# DS133-1_0-B.net
KiCad netlist of a schematic drawn in Altium Designer
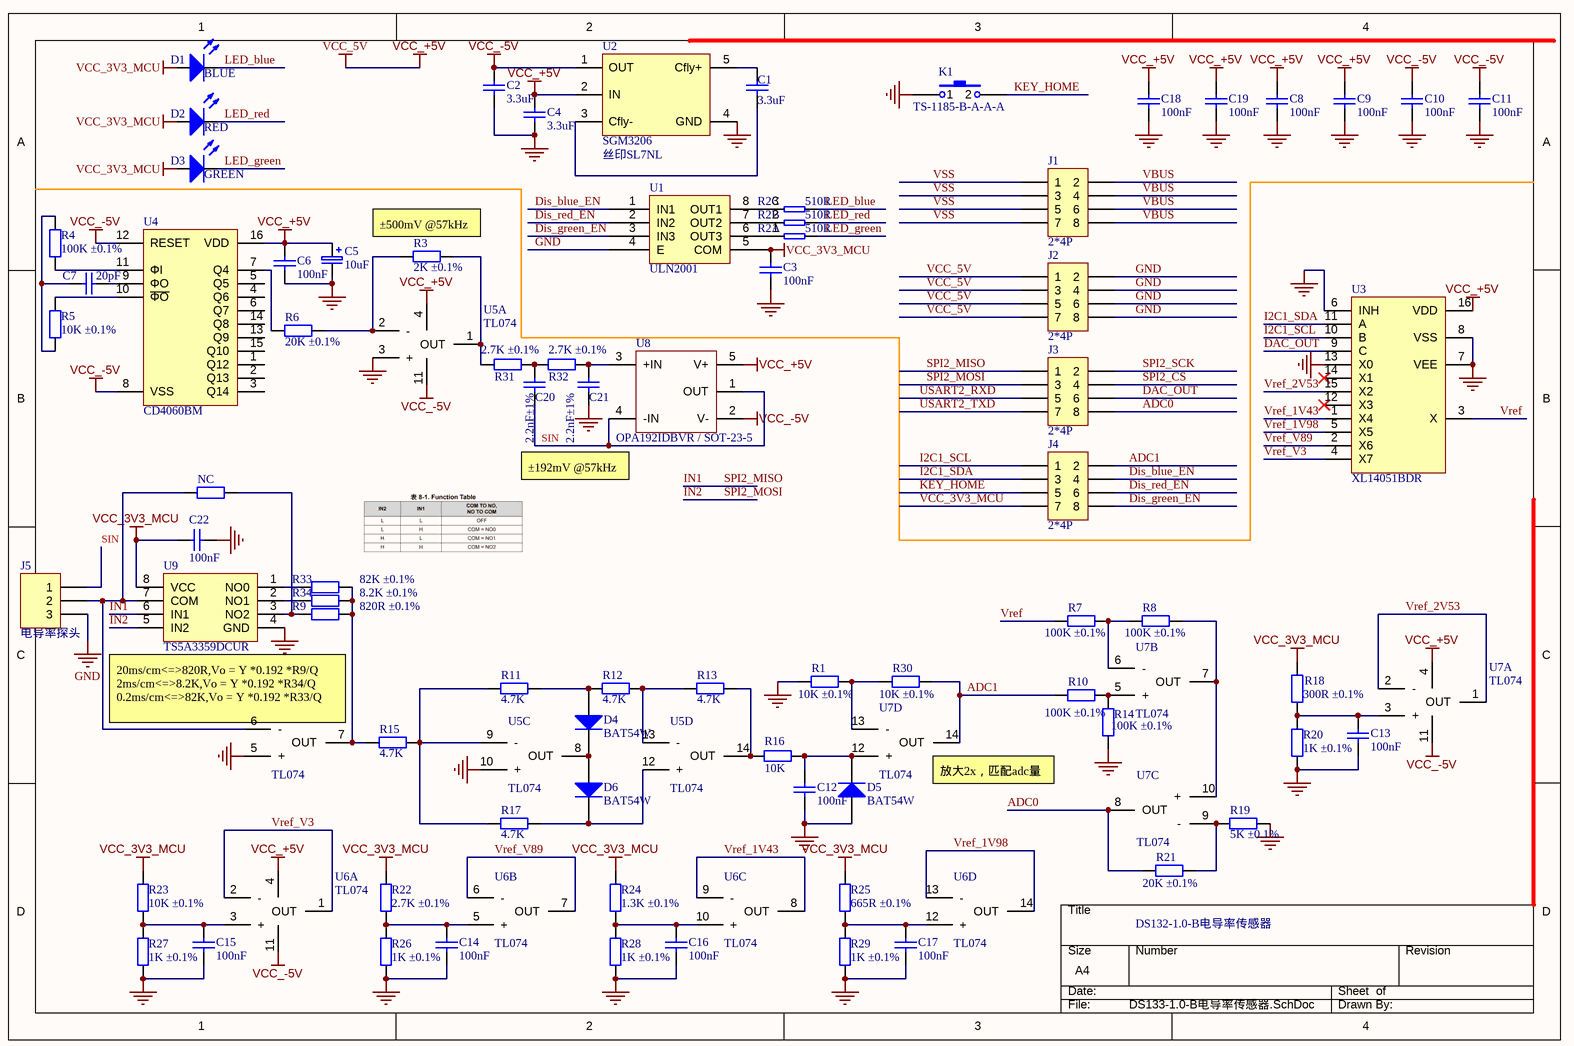
[diagram p0: DS133-1.0-B电导率传感器.SchDoc]

(export (version "E")
  (design (tool "Eeschema 10.0.6"))
  (components
    (comp (ref "C1")
      (value "3.3uF")
      (footprint "0603CAP")
      (description "贴片电容")
      (fields (field (name "Comment") "MLCC 3.3uF 50V ±10％ 0603"))
      (libsource (lib "AD_SCH") (part "MLCC 3.3uF 50V ±10％ 0603"))
    )
    (comp (ref "C2")
      (value "3.3uF")
      (footprint "0603CAP")
      (description "贴片电容")
      (libsource (lib "AD_SCH") (part "MLCC 3.3uF 50V ±10％ 0603"))
    )
    (comp (ref "C3")
      (value "100nF")
      (footprint "0603CAP")
      (description "贴片电容")
      (libsource (lib "AD_SCH") (part "MLCC 100nF 50V ±10％ 0603"))
    )
    (comp (ref "C4")
      (value "3.3uF")
      (footprint "0603CAP")
      (description "贴片电容")
      (fields (field (name "Comment") "MLCC 3.3uF 50V ±10％ 0603"))
      (libsource (lib "AD_SCH") (part "MLCC 3.3uF 50V ±10％ 0603"))
    )
    (comp (ref "C5")
      (value "10uF")
      (footprint "AVX_3216-18(1206)_SMD")
      (description "钽电容")
      (fields (field (name "Comment") "AVX_10uF/16V ±10％(C106)"))
      (libsource (lib "AD_SCH") (part "AVX_10uF/16V ±10％(C106)"))
    )
    (comp (ref "C6")
      (value "100nF")
      (footprint "0603CAP")
      (description "贴片电容")
      (fields (field (name "Comment") "SMDCAP00013"))
      (libsource (lib "AD_SCH") (part "MLCC 100nF 50V ±10％ 0603"))
    )
    (comp (ref "C7")
      (value "20pF")
      (footprint "0603CAP")
      (description "贴片电容")
      (fields (field (name "Comment") "SMDCAP00002"))
      (libsource (lib "AD_SCH") (part "MLCC 20pF 50V ±10％ 0603"))
    )
    (comp (ref "C8")
      (value "100nF")
      (footprint "0603CAP")
      (description "贴片电容")
      (libsource (lib "AD_SCH") (part "MLCC 100nF 50V ±10％ 0603"))
    )
    (comp (ref "C9")
      (value "100nF")
      (footprint "0603CAP")
      (description "贴片电容")
      (libsource (lib "AD_SCH") (part "MLCC 100nF 50V ±10％ 0603"))
    )
    (comp (ref "C10")
      (value "100nF")
      (footprint "0603CAP")
      (description "贴片电容")
      (libsource (lib "AD_SCH") (part "MLCC 100nF 50V ±10％ 0603"))
    )
    (comp (ref "C11")
      (value "100nF")
      (footprint "0603CAP")
      (description "贴片电容")
      (libsource (lib "AD_SCH") (part "MLCC 100nF 50V ±10％ 0603"))
    )
    (comp (ref "C12")
      (value "100nF")
      (footprint "0603CAP")
      (description "贴片电容")
      (libsource (lib "AD_SCH") (part "MLCC 100nF 50V ±10％ 0603"))
    )
    (comp (ref "C13")
      (value "100nF")
      (footprint "0603CAP")
      (description "贴片电容")
      (libsource (lib "AD_SCH") (part "MLCC 100nF 50V ±10％ 0603"))
    )
    (comp (ref "C14")
      (value "100nF")
      (footprint "0603CAP")
      (description "贴片电容")
      (libsource (lib "AD_SCH") (part "MLCC 100nF 50V ±10％ 0603"))
    )
    (comp (ref "C15")
      (value "100nF")
      (footprint "0603CAP")
      (description "贴片电容")
      (libsource (lib "AD_SCH") (part "MLCC 100nF 50V ±10％ 0603"))
    )
    (comp (ref "C16")
      (value "100nF")
      (footprint "0603CAP")
      (description "贴片电容")
      (libsource (lib "AD_SCH") (part "MLCC 100nF 50V ±10％ 0603"))
    )
    (comp (ref "C17")
      (value "100nF")
      (footprint "0603CAP")
      (description "贴片电容")
      (libsource (lib "AD_SCH") (part "MLCC 100nF 50V ±10％ 0603"))
    )
    (comp (ref "C18")
      (value "100nF")
      (footprint "0603CAP")
      (description "贴片电容")
      (libsource (lib "AD_SCH") (part "MLCC 100nF 50V ±10％ 0603"))
    )
    (comp (ref "C19")
      (value "100nF")
      (footprint "0603CAP")
      (description "贴片电容")
      (libsource (lib "AD_SCH") (part "MLCC 100nF 50V ±10％ 0603"))
    )
    (comp (ref "C20")
      (value "2.2nF±1%")
      (footprint "0603CAP")
      (description "贴片电容")
      (fields (field (name "Comment") "MLCC 2.2nF 50V ±1％ 0603"))
      (libsource (lib "AD_SCH") (part "MLCC 2.2nF 50V ±1％ 0603"))
    )
    (comp (ref "C21")
      (value "2.2nF±1%")
      (footprint "0603CAP")
      (description "贴片电容")
      (fields (field (name "Comment") "MLCC 2.2nF 50V ±1％ 0603"))
      (libsource (lib "AD_SCH") (part "MLCC 2.2nF 50V ±1％ 0603"))
    )
    (comp (ref "C22")
      (value "100nF")
      (footprint "0603CAP")
      (description "贴片电容")
      (libsource (lib "AD_SCH") (part "MLCC 100nF 50V ±10％ 0603"))
    )
    (comp (ref "D1")
      (value "BLUE")
      (footprint "LED_0805")
      (description "贴片LED")
      (fields (field (name "Comment") "SMDLED00010"))
      (libsource (lib "AD_SCH") (part "Chip 蓝色LED 0805"))
    )
    (comp (ref "D2")
      (value "RED")
      (footprint "LED_0805")
      (description "贴片LED")
      (fields (field (name "Comment") "SMDLED00003"))
      (libsource (lib "AD_SCH") (part "Chip 红色LED 0805"))
    )
    (comp (ref "D3")
      (value "GREEN")
      (footprint "LED_0805")
      (description "贴片LED")
      (fields (field (name "Comment") "Chip 翠绿LED 0805"))
      (libsource (lib "AD_SCH") (part "Chip 翠绿LED 0805"))
    )
    (comp (ref "D4") (value "BAT54W") (footprint "SOD-123") (libsource (lib "AD_SCH") (part "BAT54W")))
    (comp (ref "D5") (value "BAT54W") (footprint "SOD-123") (libsource (lib "AD_SCH") (part "BAT54W")))
    (comp (ref "D6") (value "BAT54W") (footprint "SOD-123") (libsource (lib "AD_SCH") (part "BAT54W")))
    (comp (ref "J1")
      (value "2*4P")
      (footprint "X1321WVS-2x04J-C40D53")
      (description "双排针2x4P 立贴 1.27mm")
      (fields (field (name "Comment") "X1321WVS-2x04J-C40D53"))
      (libsource (lib "AD_SCH") (part "X1321WVS-2x04J-C40D53"))
    )
    (comp (ref "J2")
      (value "2*4P")
      (footprint "X1321WVS-2x04J-C40D53")
      (description "双排针2x4P 立贴 1.27mm")
      (fields (field (name "Comment") "X1321WVS-2x04J-C40D53"))
      (libsource (lib "AD_SCH") (part "X1321WVS-2x04J-C40D53"))
    )
    (comp (ref "J3")
      (value "2*4P")
      (footprint "X1321WVS-2x04J-C40D53")
      (description "双排针2x4P 立贴 1.27mm")
      (fields (field (name "Comment") "X1321WVS-2x04J-C40D53"))
      (libsource (lib "AD_SCH") (part "X1321WVS-2x04J-C40D53"))
    )
    (comp (ref "J4")
      (value "2*4P")
      (footprint "X1321WVS-2x04J-C40D53")
      (description "双排针2x4P 立贴 1.27mm")
      (fields (field (name "Comment") "X1321WVS-2x04J-C40D53"))
      (libsource (lib "AD_SCH") (part "X1321WVS-2x04J-C40D53"))
    )
    (comp (ref "J5")
      (value "电导率探头")
      (footprint "SIP3")
      (description "单排直针")
      (fields (field (name "Comment") "SL000000042"))
      (libsource (lib "AD_SCH") (part "DIP3 单排直针 间距2.54mm 针长11mm 铜"))
    )
    (comp (ref "K1")
      (value "TS-1185-B-A-A-A")
      (footprint "KEY_TS-1185-x-A-A-A")
      (description "轻触开关")
      (libsource (lib "AD_SCH") (part "TS-1185-B-A-A-A"))
    )
    (comp (ref "NC")
      (value "Chip 0R 1/16W ±1％ 0603")
      (footprint "0603RES")
      (description "贴片电阻")
      (libsource (lib "AD_SCH") (part "Chip 0R 1/16W ±1％ 0603"))
    )
    (comp (ref "R1")
      (value "10K ±0.1%")
      (footprint "0603RES")
      (fields (field (name "Comment") "Chip 10K 1/10W ±0.1％ 0603"))
      (libsource (lib "AD_SCH") (part "Chip 10K 1/10W ±0.1％ 0603"))
    )
    (comp (ref "R2")
      (value "510R")
      (footprint "0603RES_Pack4")
      (description "贴片排阻")
      (fields (field (name "Comment") "SMDRES05003"))
      (libsource (lib "AD_SCH") (part "Chip R*4 510R 1/16W ±5％ 0603"))
    )
    (comp (ref "R3")
      (value "2K ±0.1%")
      (footprint "0603RES")
      (fields (field (name "Comment") "Chip 2K 1/10W ±0.1％ 0603"))
      (libsource (lib "AD_SCH") (part "Chip 2K 1/10W ±0.1％ 0603"))
    )
    (comp (ref "R4")
      (value "100K ±0.1%")
      (footprint "0603RES")
      (libsource (lib "AD_SCH") (part "Chip 100K 1/10W ±0.1％ 0603"))
    )
    (comp (ref "R5")
      (value "10K ±0.1%")
      (footprint "0603RES")
      (fields (field (name "Comment") "Chip 10K 1/10W ±0.1％ 0603"))
      (libsource (lib "") (part "Chip 10K 1/10W ±0.1％ 0603_1"))
    )
    (comp (ref "R6")
      (value "20K ±0.1%")
      (footprint "0603RES")
      (fields (field (name "Comment") "Chip 20K 1/10W ±0.1％ 0603"))
      (libsource (lib "AD_SCH") (part "Chip 20K 1/10W ±0.1％ 0603"))
    )
    (comp (ref "R7")
      (value "100K ±0.1%")
      (footprint "0603RES")
      (fields (field (name "Comment") "Chip 100K 1/10W ±0.1％ 0603"))
      (libsource (lib "") (part "Chip 100K 1/10W ±0.1％ 0603_1"))
    )
    (comp (ref "R8")
      (value "100K ±0.1%")
      (footprint "0603RES")
      (fields (field (name "Comment") "Chip 100K 1/10W ±0.1％ 0603"))
      (libsource (lib "") (part "Chip 100K 1/10W ±0.1％ 0603_2"))
    )
    (comp (ref "R9")
      (value "820R ±0.1%")
      (footprint "0603RES")
      (fields (field (name "Comment") "Chip 820R 1/10W ±0.1％ 0603"))
      (libsource (lib "AD_SCH") (part "Chip 820R 1/10W ±0.1％ 0603"))
    )
    (comp (ref "R10")
      (value "100K ±0.1%")
      (footprint "0603RES")
      (fields (field (name "Comment") "Chip 100K 1/10W ±0.1％ 0603"))
      (libsource (lib "") (part "Chip 100K 1/10W ±0.1％ 0603_1"))
    )
    (comp (ref "R11")
      (value "4.7K")
      (footprint "0603RES")
      (description "贴片电阻")
      (fields (field (name "Comment") "SMDRES00047"))
      (libsource (lib "AD_SCH") (part "Chip 4.7K 1/10W ±1％ 0603"))
    )
    (comp (ref "R12")
      (value "4.7K")
      (footprint "0603RES")
      (description "贴片电阻")
      (fields (field (name "Comment") "SMDRES00047"))
      (libsource (lib "AD_SCH") (part "Chip 4.7K 1/10W ±1％ 0603"))
    )
    (comp (ref "R13")
      (value "4.7K")
      (footprint "0603RES")
      (description "贴片电阻")
      (fields (field (name "Comment") "SMDRES00047"))
      (libsource (lib "AD_SCH") (part "Chip 4.7K 1/10W ±1％ 0603"))
    )
    (comp (ref "R14")
      (value "100K ±0.1%")
      (footprint "0603RES")
      (fields (field (name "Comment") "Chip 100K 1/10W ±0.1％ 0603"))
      (libsource (lib "AD_SCH") (part "Chip 100K 1/10W ±0.1％ 0603"))
    )
    (comp (ref "R15")
      (value "4.7K")
      (footprint "0603RES")
      (description "贴片电阻")
      (fields (field (name "Comment") "SMDRES00047"))
      (libsource (lib "AD_SCH") (part "Chip 4.7K 1/10W ±1％ 0603"))
    )
    (comp (ref "R16")
      (value "10K")
      (footprint "0603RES")
      (description "贴片电阻")
      (fields (field (name "Comment") "Chip 10K 1/16W ±1％ 0603"))
      (libsource (lib "AD_SCH") (part "Chip 10K 1/16W ±1％ 0603"))
    )
    (comp (ref "R17")
      (value "4.7K")
      (footprint "0603RES")
      (description "贴片电阻")
      (fields (field (name "Comment") "SMDRES00047"))
      (libsource (lib "AD_SCH") (part "Chip 4.7K 1/10W ±1％ 0603"))
    )
    (comp (ref "R18")
      (value "300R ±0.1%")
      (footprint "0603RES")
      (libsource (lib "AD_SCH") (part "Chip 300R 1/10W ±0.1％ 0603"))
    )
    (comp (ref "R19")
      (value "5K ±0.1%")
      (footprint "0603RES")
      (fields (field (name "Comment") "Chip 5K 1/10W ±0.1％ 0603"))
      (libsource (lib "AD_SCH") (part "Chip 5K 1/10W ±0.1％ 0603"))
    )
    (comp (ref "R20")
      (value "1K ±0.1%")
      (footprint "0603RES")
      (fields (field (name "Comment") "Chip 1K 1/10W ±0.1％ 0603"))
      (libsource (lib "AD_SCH") (part "Chip 1K 1/10W ±0.1％ 0603"))
    )
    (comp (ref "R21")
      (value "20K ±0.1%")
      (footprint "0603RES")
      (fields (field (name "Comment") "Chip 20K 1/10W ±0.1％ 0603"))
      (libsource (lib "AD_SCH") (part "Chip 20K 1/10W ±0.1％ 0603"))
    )
    (comp (ref "R22")
      (value "2.7K ±0.1%")
      (footprint "0603RES")
      (fields (field (name "Comment") "Chip 2.7K 1/10W ±0.1％ 0603"))
      (libsource (lib "") (part "Chip 2.7K 1/10W ±0.1％ 0603_1"))
    )
    (comp (ref "R23")
      (value "10K ±0.1%")
      (footprint "0603RES")
      (fields (field (name "Comment") "Chip 10K 1/10W ±0.1％ 0603"))
      (libsource (lib "") (part "Chip 10K 1/10W ±0.1％ 0603_1"))
    )
    (comp (ref "R24")
      (value "1.3K ±0.1%")
      (footprint "0603RES")
      (fields (field (name "Comment") "Chip 1.3K 1/10W ±0.1％ 0603"))
      (libsource (lib "AD_SCH") (part "Chip 1.3K 1/10W ±0.1％ 0603"))
    )
    (comp (ref "R25")
      (value "665R ±0.1%")
      (footprint "0603RES")
      (fields (field (name "Comment") "Chip 665R 1/10W ±0.1％ 0603"))
      (libsource (lib "AD_SCH") (part "Chip 665R 1/10W ±0.1％ 0603"))
    )
    (comp (ref "R26")
      (value "1K ±0.1%")
      (footprint "0603RES")
      (fields (field (name "Comment") "Chip 1K 1/10W ±0.1％ 0603"))
      (libsource (lib "AD_SCH") (part "Chip 1K 1/10W ±0.1％ 0603"))
    )
    (comp (ref "R27")
      (value "1K ±0.1%")
      (footprint "0603RES")
      (fields (field (name "Comment") "Chip 1K 1/10W ±0.1％ 0603"))
      (libsource (lib "AD_SCH") (part "Chip 1K 1/10W ±0.1％ 0603"))
    )
    (comp (ref "R28")
      (value "1K ±0.1%")
      (footprint "0603RES")
      (fields (field (name "Comment") "Chip 1K 1/10W ±0.1％ 0603"))
      (libsource (lib "AD_SCH") (part "Chip 1K 1/10W ±0.1％ 0603"))
    )
    (comp (ref "R29")
      (value "1K ±0.1%")
      (footprint "0603RES")
      (fields (field (name "Comment") "Chip 1K 1/10W ±0.1％ 0603"))
      (libsource (lib "AD_SCH") (part "Chip 1K 1/10W ±0.1％ 0603"))
    )
    (comp (ref "R30")
      (value "10K ±0.1%")
      (footprint "0603RES")
      (fields (field (name "Comment") "Chip 10K 1/10W ±0.1％ 0603"))
      (libsource (lib "AD_SCH") (part "Chip 10K 1/10W ±0.1％ 0603"))
    )
    (comp (ref "R31")
      (value "2.7K ±0.1%")
      (footprint "0603RES")
      (fields (field (name "Comment") "Chip 2.7K 1/10W ±0.1％ 0603"))
      (libsource (lib "AD_SCH") (part "Chip 2.7K 1/10W ±0.1％ 0603"))
    )
    (comp (ref "R32")
      (value "2.7K ±0.1%")
      (footprint "0603RES")
      (fields (field (name "Comment") "Chip 2.7K 1/10W ±0.1％ 0603"))
      (libsource (lib "AD_SCH") (part "Chip 2.7K 1/10W ±0.1％ 0603"))
    )
    (comp (ref "R33")
      (value "82K ±0.1%")
      (footprint "0603RES")
      (fields (field (name "Comment") "SMDRES00096"))
      (libsource (lib "AD_SCH") (part "Chip 82K 1/10W ±0.1％ 0603"))
    )
    (comp (ref "R34")
      (value "8.2K ±0.1%")
      (footprint "0603RES")
      (fields (field (name "Comment") "Chip 8.2k 1/10W ±0.1％ 0603"))
      (libsource (lib "AD_SCH") (part "Chip 8.2k 1/10W ±0.1％ 0603"))
    )
    (comp (ref "U1")
      (value "ULN2001")
      (footprint "SO-8")
      (description "电机驱动芯片")
      (fields (field (name "Comment") "SMDIC000018"))
      (libsource (lib "AD_SCH") (part "ULN2001 SOP-8"))
    )
    (comp (ref "U2")
      (value "SGM3206")
      (footprint "SOT23-5")
      (description "电荷泵芯片")
      (fields (field (name "ALTIUM_VALUE") "丝印SL7NL"))
      (libsource (lib "AD_SCH") (part "SGM3206"))
    )
    (comp (ref "U3")
      (value "XL14051BDR")
      (footprint "SO-16")
      (description "XINLUDA(信路达)\r\nXL14051BDR\r\nSOP-16​")
      (libsource (lib "AD_SCH") (part "XL14051BDR"))
    )
    (comp (ref "U4")
      (value "CD4060BM")
      (footprint "SO-16")
      (description "HGSEMI(华冠)\r\nCD4060BM/TR\r\nSOP-16")
      (libsource (lib "AD_SCH") (part "CD4060BM"))
    )
    (comp (ref "U5")
      (value "TL074")
      (footprint "SO-14")
      (description "TI\r\nTL074CDR\r\nSOIC-14")
      (libsource (lib "AD_SCH") (part "TL074"))
    )
    (comp (ref "U6")
      (value "TL074")
      (footprint "SO-14")
      (description "TI\r\nTL074CDR\r\nSOIC-14")
      (libsource (lib "AD_SCH") (part "TL074"))
    )
    (comp (ref "U7")
      (value "TL074")
      (footprint "SO-14")
      (description "TI\r\nTL074CDR\r\nSOIC-14")
      (libsource (lib "AD_SCH") (part "TL074"))
    )
    (comp (ref "U8")
      (value "OPA192IDBVR / SOT-23-5")
      (footprint "SOT23-5")
      (description "低失调电压: 65 µV（最大值）\r\n低输入偏置电流: 1 pA（最大值）\r\n单电源供电：2.7 V至5.5 V")
      (libsource (lib "AD_SCH") (part "AD8605"))
    )
    (comp (ref "U9")
      (value "TS5A3359DCUR")
      (footprint "VSSOP-8")
      (description "单刀三掷(SP3T)模拟开关")
      (libsource (lib "AD_SCH") (part "TS5A3359DCUR"))
    )
  )
  (nets
    (net (code "1") (name "/ADC0") (class "Default")
      (node (ref "J3") (pin "8") (pinfunction "8_8") (pintype "passive"))
      (node (ref "R21") (pin "1") (pinfunction "1_1") (pintype "passive"))
      (node (ref "U7") (pin "8") (pinfunction "OUT_8") (pintype "passive"))
    )
    (net (code "2") (name "/ADC1") (class "Default")
      (node (ref "J4") (pin "2") (pinfunction "2_2") (pintype "passive"))
      (node (ref "R10") (pin "1") (pinfunction "1_1") (pintype "passive"))
      (node (ref "R30") (pin "2") (pinfunction "2_2") (pintype "passive"))
      (node (ref "U7") (pin "14") (pinfunction "OUT_14") (pintype "passive"))
    )
    (net (code "3") (name "/DAC_OUT") (class "Default")
      (node (ref "J3") (pin "6") (pinfunction "6_6") (pintype "passive"))
      (node (ref "U3") (pin "9") (pinfunction "C_9") (pintype "passive"))
    )
    (net (code "4") (name "/Dis_blue_EN") (class "Default")
      (node (ref "J4") (pin "4") (pinfunction "4_4") (pintype "passive"))
      (node (ref "U1") (pin "1") (pinfunction "IN1_1") (pintype "passive"))
    )
    (net (code "5") (name "/Dis_green_EN") (class "Default")
      (node (ref "J4") (pin "8") (pinfunction "8_8") (pintype "passive"))
      (node (ref "U1") (pin "3") (pinfunction "IN3_3") (pintype "passive"))
    )
    (net (code "6") (name "/Dis_red_EN") (class "Default")
      (node (ref "J4") (pin "6") (pinfunction "6_6") (pintype "passive"))
      (node (ref "U1") (pin "2") (pinfunction "IN2_2") (pintype "passive"))
    )
    (net (code "7") (name "/I2C1_SCL") (class "Default")
      (node (ref "J4") (pin "1") (pinfunction "1_1") (pintype "passive"))
      (node (ref "U3") (pin "10") (pinfunction "B_10") (pintype "passive"))
    )
    (net (code "8") (name "/I2C1_SDA") (class "Default")
      (node (ref "J4") (pin "3") (pinfunction "3_3") (pintype "passive"))
      (node (ref "U3") (pin "11") (pinfunction "A_11") (pintype "passive"))
    )
    (net (code "9") (name "/IN1") (class "Default")
      (node (ref "J3") (pin "1") (pinfunction "1_1") (pintype "passive"))
      (node (ref "U9") (pin "6") (pinfunction "IN1_6") (pintype "passive"))
    )
    (net (code "10") (name "/IN2") (class "Default")
      (node (ref "J3") (pin "3") (pinfunction "3_3") (pintype "passive"))
      (node (ref "U9") (pin "5") (pinfunction "IN2_5") (pintype "passive"))
    )
    (net (code "11") (name "/KEY_HOME") (class "Default")
      (node (ref "J4") (pin "5") (pinfunction "5_5") (pintype "passive"))
      (node (ref "K1") (pin "2") (pinfunction "2_2") (pintype "passive"))
    )
    (net (code "12") (name "/LED_blue") (class "Default")
      (node (ref "D1") (pin "2") (pinfunction "K_2") (pintype "passive"))
      (node (ref "R2") (pin "6") (pinfunction "6_6") (pintype "passive"))
    )
    (net (code "13") (name "/LED_green") (class "Default")
      (node (ref "D3") (pin "2") (pinfunction "K_2") (pintype "passive"))
      (node (ref "R2") (pin "8") (pinfunction "8_8") (pintype "passive"))
    )
    (net (code "14") (name "/LED_red") (class "Default")
      (node (ref "D2") (pin "2") (pinfunction "K_2") (pintype "passive"))
      (node (ref "R2") (pin "7") (pinfunction "7_7") (pintype "passive"))
    )
    (net (code "15") (name "/SIN") (class "Default")
      (node (ref "C20") (pin "1") (pinfunction "1_1") (pintype "passive"))
      (node (ref "J5") (pin "1") (pinfunction "1_1") (pintype "passive"))
      (node (ref "U8") (pin "1") (pinfunction "OUT_1") (pintype "passive"))
      (node (ref "U8") (pin "4") (pinfunction "-IN_4") (pintype "passive"))
    )
    (net (code "16") (name "/SPI2_CS") (class "Default")
      (node (ref "J3") (pin "4") (pinfunction "4_4") (pintype "passive"))
    )
    (net (code "17") (name "/SPI2_SCK") (class "Default")
      (node (ref "J3") (pin "2") (pinfunction "2_2") (pintype "passive"))
    )
    (net (code "18") (name "/USART2_RXD") (class "Default")
      (node (ref "J3") (pin "5") (pinfunction "5_5") (pintype "passive"))
    )
    (net (code "19") (name "/USART2_TXD") (class "Default")
      (node (ref "J3") (pin "7") (pinfunction "7_7") (pintype "passive"))
    )
    (net (code "20") (name "/VBUS") (class "Default")
      (node (ref "J1") (pin "2") (pinfunction "2_2") (pintype "passive"))
      (node (ref "J1") (pin "4") (pinfunction "4_4") (pintype "passive"))
      (node (ref "J1") (pin "6") (pinfunction "6_6") (pintype "passive"))
      (node (ref "J1") (pin "8") (pinfunction "8_8") (pintype "passive"))
    )
    (net (code "21") (name "/VSS") (class "Default")
      (node (ref "J1") (pin "1") (pinfunction "1_1") (pintype "passive"))
      (node (ref "J1") (pin "3") (pinfunction "3_3") (pintype "passive"))
      (node (ref "J1") (pin "5") (pinfunction "5_5") (pintype "passive"))
      (node (ref "J1") (pin "7") (pinfunction "7_7") (pintype "passive"))
    )
    (net (code "22") (name "/Vref") (class "Default")
      (node (ref "R7") (pin "1") (pinfunction "1_1") (pintype "passive"))
      (node (ref "U3") (pin "3") (pinfunction "X_3") (pintype "passive"))
    )
    (net (code "23") (name "/Vref_1V43") (class "Default")
      (node (ref "U3") (pin "1") (pinfunction "X4_1") (pintype "passive"))
      (node (ref "U6") (pin "8") (pinfunction "OUT_8") (pintype "passive"))
      (node (ref "U6") (pin "9") (pinfunction "-_9") (pintype "passive"))
    )
    (net (code "24") (name "/Vref_1V98") (class "Default")
      (node (ref "U3") (pin "5") (pinfunction "X5_5") (pintype "passive"))
      (node (ref "U6") (pin "13") (pinfunction "-_13") (pintype "passive"))
      (node (ref "U6") (pin "14") (pinfunction "OUT_14") (pintype "passive"))
    )
    (net (code "25") (name "/Vref_2V53") (class "Default")
      (node (ref "U3") (pin "15") (pinfunction "X2_15") (pintype "passive"))
      (node (ref "U7") (pin "1") (pinfunction "OUT_1") (pintype "passive"))
      (node (ref "U7") (pin "2") (pinfunction "-_2") (pintype "passive"))
    )
    (net (code "26") (name "/Vref_V3") (class "Default")
      (node (ref "U3") (pin "4") (pinfunction "X7_4") (pintype "passive"))
      (node (ref "U6") (pin "1") (pinfunction "OUT_1") (pintype "passive"))
      (node (ref "U6") (pin "2") (pinfunction "-_2") (pintype "passive"))
    )
    (net (code "27") (name "/Vref_V89") (class "Default")
      (node (ref "U3") (pin "2") (pinfunction "X6_2") (pintype "passive"))
      (node (ref "U6") (pin "6") (pinfunction "-_6") (pintype "passive"))
      (node (ref "U6") (pin "7") (pinfunction "OUT_7") (pintype "passive"))
    )
    (net (code "28") (name "GND") (class "Default")
      (node (ref "C10") (pin "1") (pinfunction "1_1") (pintype "passive"))
      (node (ref "C11") (pin "1") (pinfunction "1_1") (pintype "passive"))
      (node (ref "C12") (pin "1") (pinfunction "1_1") (pintype "passive"))
      (node (ref "C13") (pin "2") (pinfunction "2_2") (pintype "passive"))
      (node (ref "C14") (pin "2") (pinfunction "2_2") (pintype "passive"))
      (node (ref "C15") (pin "2") (pinfunction "2_2") (pintype "passive"))
      (node (ref "C16") (pin "2") (pinfunction "2_2") (pintype "passive"))
      (node (ref "C17") (pin "2") (pinfunction "2_2") (pintype "passive"))
      (node (ref "C18") (pin "1") (pinfunction "1_1") (pintype "passive"))
      (node (ref "C19") (pin "1") (pinfunction "1_1") (pintype "passive"))
      (node (ref "C2") (pin "2") (pinfunction "2_2") (pintype "passive"))
      (node (ref "C21") (pin "1") (pinfunction "1_1") (pintype "passive"))
      (node (ref "C22") (pin "2") (pinfunction "2_2") (pintype "passive"))
      (node (ref "C3") (pin "1") (pinfunction "1_1") (pintype "passive"))
      (node (ref "C4") (pin "2") (pinfunction "2_2") (pintype "passive"))
      (node (ref "C5") (pin "2") (pinfunction "2_2") (pintype "passive"))
      (node (ref "C6") (pin "2") (pinfunction "2_2") (pintype "passive"))
      (node (ref "C8") (pin "1") (pinfunction "1_1") (pintype "passive"))
      (node (ref "C9") (pin "1") (pinfunction "1_1") (pintype "passive"))
      (node (ref "D5") (pin "1") (pinfunction "A_1") (pintype "passive"))
      (node (ref "J2") (pin "2") (pinfunction "2_2") (pintype "passive"))
      (node (ref "J2") (pin "4") (pinfunction "4_4") (pintype "passive"))
      (node (ref "J2") (pin "6") (pinfunction "6_6") (pintype "passive"))
      (node (ref "J2") (pin "8") (pinfunction "8_8") (pintype "passive"))
      (node (ref "J5") (pin "3") (pinfunction "3_3") (pintype "passive"))
      (node (ref "K1") (pin "1") (pinfunction "1_1") (pintype "passive"))
      (node (ref "R1") (pin "1") (pinfunction "1_1") (pintype "passive"))
      (node (ref "R14") (pin "1") (pinfunction "1_1") (pintype "passive"))
      (node (ref "R19") (pin "2") (pinfunction "2_2") (pintype "passive"))
      (node (ref "R20") (pin "1") (pinfunction "1_1") (pintype "passive"))
      (node (ref "R26") (pin "1") (pinfunction "1_1") (pintype "passive"))
      (node (ref "R27") (pin "1") (pinfunction "1_1") (pintype "passive"))
      (node (ref "R28") (pin "1") (pinfunction "1_1") (pintype "passive"))
      (node (ref "R29") (pin "1") (pinfunction "1_1") (pintype "passive"))
      (node (ref "U1") (pin "4") (pinfunction "E_4") (pintype "passive"))
      (node (ref "U2") (pin "4") (pinfunction "GND_4") (pintype "passive"))
      (node (ref "U3") (pin "13") (pinfunction "X0_13") (pintype "passive"))
      (node (ref "U3") (pin "6") (pinfunction "INH_6") (pintype "passive"))
      (node (ref "U3") (pin "7") (pinfunction "VEE_7") (pintype "passive"))
      (node (ref "U3") (pin "8") (pinfunction "VSS_8") (pintype "passive"))
      (node (ref "U5") (pin "10") (pinfunction "+_10") (pintype "passive"))
      (node (ref "U5") (pin "3") (pinfunction "+_3") (pintype "passive"))
      (node (ref "U5") (pin "5") (pinfunction "+_5") (pintype "passive"))
      (node (ref "U9") (pin "4") (pinfunction "GND_4") (pintype "passive"))
    )
    (net (code "29") (name "Net-(C7-Pad2)") (class "Default")
      (node (ref "C7") (pin "2") (pinfunction "2_2") (pintype "passive"))
      (node (ref "R4") (pin "2") (pinfunction "2_2") (pintype "passive"))
      (node (ref "R5") (pin "1") (pinfunction "1_1") (pintype "passive"))
    )
    (net (code "30") (name "Net-(C20-Pad2)") (class "Default")
      (node (ref "C20") (pin "2") (pinfunction "2_2") (pintype "passive"))
      (node (ref "R31") (pin "2") (pinfunction "2_2") (pintype "passive"))
      (node (ref "R32") (pin "1") (pinfunction "1_1") (pintype "passive"))
    )
    (net (code "31") (name "Net-(D4-A)") (class "Default")
      (node (ref "D4") (pin "1") (pinfunction "A_1") (pintype "passive"))
      (node (ref "R11") (pin "2") (pinfunction "2_2") (pintype "passive"))
      (node (ref "R12") (pin "1") (pinfunction "1_1") (pintype "passive"))
    )
    (net (code "32") (name "Net-(D4-K)") (class "Default")
      (node (ref "D4") (pin "2") (pinfunction "K_2") (pintype "passive"))
      (node (ref "D6") (pin "1") (pinfunction "A_1") (pintype "passive"))
      (node (ref "U5") (pin "8") (pinfunction "OUT_8") (pintype "passive"))
    )
    (net (code "33") (name "Net-(D5-K)") (class "Default")
      (node (ref "C12") (pin "2") (pinfunction "2_2") (pintype "passive"))
      (node (ref "D5") (pin "2") (pinfunction "K_2") (pintype "passive"))
      (node (ref "R16") (pin "2") (pinfunction "2_2") (pintype "passive"))
      (node (ref "U7") (pin "12") (pinfunction "+_12") (pintype "passive"))
    )
    (net (code "34") (name "Net-(D6-K)") (class "Default")
      (node (ref "D6") (pin "2") (pinfunction "K_2") (pintype "passive"))
      (node (ref "R17") (pin "2") (pinfunction "2_2") (pintype "passive"))
      (node (ref "U5") (pin "12") (pinfunction "+_12") (pintype "passive"))
    )
    (net (code "35") (name "Net-(U1-OUT1)") (class "Default")
      (node (ref "R2") (pin "3") (pinfunction "3_3") (pintype "passive"))
      (node (ref "U1") (pin "8") (pinfunction "OUT1_8") (pintype "passive"))
    )
    (net (code "36") (name "Net-(U1-OUT2)") (class "Default")
      (node (ref "R2") (pin "2") (pinfunction "2_2") (pintype "passive"))
      (node (ref "U1") (pin "7") (pinfunction "OUT2_7") (pintype "passive"))
    )
    (net (code "37") (name "Net-(U1-OUT3)") (class "Default")
      (node (ref "R2") (pin "1") (pinfunction "1_1") (pintype "passive"))
      (node (ref "U1") (pin "6") (pinfunction "OUT3_6") (pintype "passive"))
    )
    (net (code "38") (name "Net-(U2-Cfly+)") (class "Default")
      (node (ref "C1") (pin "2") (pinfunction "2_2") (pintype "passive"))
      (node (ref "U2") (pin "5") (pinfunction "Cfly+_5") (pintype "passive"))
    )
    (net (code "39") (name "Net-(U2-Cfly-)") (class "Default")
      (node (ref "C1") (pin "1") (pinfunction "1_1") (pintype "passive"))
      (node (ref "U2") (pin "3") (pinfunction "Cfly-_3") (pintype "passive"))
    )
    (net (code "40") (name "Net-(U4-Q4)") (class "Default")
      (node (ref "R6") (pin "1") (pinfunction "1_1") (pintype "passive"))
      (node (ref "U4") (pin "7") (pinfunction "Q4_7") (pintype "passive"))
    )
    (net (code "41") (name "Net-(U4-~{ΦO})") (class "Default")
      (node (ref "R5") (pin "2") (pinfunction "2_2") (pintype "passive"))
      (node (ref "U4") (pin "10") (pinfunction "~{ΦO}_10") (pintype "passive"))
    )
    (net (code "42") (name "Net-(U4-ΦI)") (class "Default")
      (node (ref "R4") (pin "1") (pinfunction "1_1") (pintype "passive"))
      (node (ref "U4") (pin "11") (pinfunction "ΦI_11") (pintype "passive"))
    )
    (net (code "43") (name "Net-(U4-ΦO)") (class "Default")
      (node (ref "C7") (pin "1") (pinfunction "1_1") (pintype "passive"))
      (node (ref "U4") (pin "9") (pinfunction "ΦO_9") (pintype "passive"))
    )
    (net (code "44") (name "Net-(U5A--)") (class "Default")
      (node (ref "R3") (pin "1") (pinfunction "1_1") (pintype "passive"))
      (node (ref "R6") (pin "2") (pinfunction "2_2") (pintype "passive"))
      (node (ref "U5") (pin "2") (pinfunction "-_2") (pintype "passive"))
    )
    (net (code "45") (name "Net-(U5A-OUT)") (class "Default")
      (node (ref "R3") (pin "2") (pinfunction "2_2") (pintype "passive"))
      (node (ref "R31") (pin "1") (pinfunction "1_1") (pintype "passive"))
      (node (ref "U5") (pin "1") (pinfunction "OUT_1") (pintype "passive"))
    )
    (net (code "46") (name "Net-(U5B--)") (class "Default")
      (node (ref "J5") (pin "2") (pinfunction "2_2") (pintype "passive"))
      (node (ref "NC") (pin "1") (pinfunction "1_1") (pintype "passive"))
      (node (ref "U5") (pin "6") (pinfunction "-_6") (pintype "passive"))
      (node (ref "U9") (pin "7") (pinfunction "COM_7") (pintype "passive"))
    )
    (net (code "47") (name "Net-(U5B-OUT)") (class "Default")
      (node (ref "R15") (pin "1") (pinfunction "1_1") (pintype "passive"))
      (node (ref "R33") (pin "2") (pinfunction "2_2") (pintype "passive"))
      (node (ref "R34") (pin "2") (pinfunction "2_2") (pintype "passive"))
      (node (ref "R9") (pin "2") (pinfunction "2_2") (pintype "passive"))
      (node (ref "U5") (pin "7") (pinfunction "OUT_7") (pintype "passive"))
    )
    (net (code "48") (name "Net-(U5C--)") (class "Default")
      (node (ref "R11") (pin "1") (pinfunction "1_1") (pintype "passive"))
      (node (ref "R15") (pin "2") (pinfunction "2_2") (pintype "passive"))
      (node (ref "R17") (pin "1") (pinfunction "1_1") (pintype "passive"))
      (node (ref "U5") (pin "9") (pinfunction "-_9") (pintype "passive"))
    )
    (net (code "49") (name "Net-(U5D--)") (class "Default")
      (node (ref "R12") (pin "2") (pinfunction "2_2") (pintype "passive"))
      (node (ref "R13") (pin "1") (pinfunction "1_1") (pintype "passive"))
      (node (ref "U5") (pin "13") (pinfunction "-_13") (pintype "passive"))
    )
    (net (code "50") (name "Net-(U5D-OUT)") (class "Default")
      (node (ref "R13") (pin "2") (pinfunction "2_2") (pintype "passive"))
      (node (ref "R16") (pin "1") (pinfunction "1_1") (pintype "passive"))
      (node (ref "U5") (pin "14") (pinfunction "OUT_14") (pintype "passive"))
    )
    (net (code "51") (name "Net-(U6A-+)") (class "Default")
      (node (ref "C15") (pin "1") (pinfunction "1_1") (pintype "passive"))
      (node (ref "R23") (pin "1") (pinfunction "1_1") (pintype "passive"))
      (node (ref "R27") (pin "2") (pinfunction "2_2") (pintype "passive"))
      (node (ref "U6") (pin "3") (pinfunction "+_3") (pintype "passive"))
    )
    (net (code "52") (name "Net-(U6B-+)") (class "Default")
      (node (ref "C14") (pin "1") (pinfunction "1_1") (pintype "passive"))
      (node (ref "R22") (pin "1") (pinfunction "1_1") (pintype "passive"))
      (node (ref "R26") (pin "2") (pinfunction "2_2") (pintype "passive"))
      (node (ref "U6") (pin "5") (pinfunction "+_5") (pintype "passive"))
    )
    (net (code "53") (name "Net-(U6C-+)") (class "Default")
      (node (ref "C16") (pin "1") (pinfunction "1_1") (pintype "passive"))
      (node (ref "R24") (pin "1") (pinfunction "1_1") (pintype "passive"))
      (node (ref "R28") (pin "2") (pinfunction "2_2") (pintype "passive"))
      (node (ref "U6") (pin "10") (pinfunction "+_10") (pintype "passive"))
    )
    (net (code "54") (name "Net-(U6D-+)") (class "Default")
      (node (ref "C17") (pin "1") (pinfunction "1_1") (pintype "passive"))
      (node (ref "R25") (pin "1") (pinfunction "1_1") (pintype "passive"))
      (node (ref "R29") (pin "2") (pinfunction "2_2") (pintype "passive"))
      (node (ref "U6") (pin "12") (pinfunction "+_12") (pintype "passive"))
    )
    (net (code "55") (name "Net-(U7A-+)") (class "Default")
      (node (ref "C13") (pin "1") (pinfunction "1_1") (pintype "passive"))
      (node (ref "R18") (pin "1") (pinfunction "1_1") (pintype "passive"))
      (node (ref "R20") (pin "2") (pinfunction "2_2") (pintype "passive"))
      (node (ref "U7") (pin "3") (pinfunction "+_3") (pintype "passive"))
    )
    (net (code "56") (name "Net-(U7B-+)") (class "Default")
      (node (ref "R10") (pin "2") (pinfunction "2_2") (pintype "passive"))
      (node (ref "R14") (pin "2") (pinfunction "2_2") (pintype "passive"))
      (node (ref "U7") (pin "5") (pinfunction "+_5") (pintype "passive"))
    )
    (net (code "57") (name "Net-(U7B--)") (class "Default")
      (node (ref "R7") (pin "2") (pinfunction "2_2") (pintype "passive"))
      (node (ref "R8") (pin "2") (pinfunction "2_2") (pintype "passive"))
      (node (ref "U7") (pin "6") (pinfunction "-_6") (pintype "passive"))
    )
    (net (code "58") (name "Net-(U7B-OUT)") (class "Default")
      (node (ref "R8") (pin "1") (pinfunction "1_1") (pintype "passive"))
      (node (ref "U7") (pin "10") (pinfunction "+_10") (pintype "passive"))
      (node (ref "U7") (pin "7") (pinfunction "OUT_7") (pintype "passive"))
    )
    (net (code "59") (name "Net-(U7C--)") (class "Default")
      (node (ref "R19") (pin "1") (pinfunction "1_1") (pintype "passive"))
      (node (ref "R21") (pin "2") (pinfunction "2_2") (pintype "passive"))
      (node (ref "U7") (pin "9") (pinfunction "-_9") (pintype "passive"))
    )
    (net (code "60") (name "Net-(U7D--)") (class "Default")
      (node (ref "R1") (pin "2") (pinfunction "2_2") (pintype "passive"))
      (node (ref "R30") (pin "1") (pinfunction "1_1") (pintype "passive"))
      (node (ref "U7") (pin "13") (pinfunction "-_13") (pintype "passive"))
    )
    (net (code "61") (name "Net-(U8-+IN)") (class "Default")
      (node (ref "C21") (pin "2") (pinfunction "2_2") (pintype "passive"))
      (node (ref "R32") (pin "2") (pinfunction "2_2") (pintype "passive"))
      (node (ref "U8") (pin "3") (pinfunction "+IN_3") (pintype "passive"))
    )
    (net (code "62") (name "Net-(U9-NO0)") (class "Default")
      (node (ref "R33") (pin "1") (pinfunction "1_1") (pintype "passive"))
      (node (ref "U9") (pin "1") (pinfunction "NO0_1") (pintype "passive"))
    )
    (net (code "63") (name "Net-(U9-NO1)") (class "Default")
      (node (ref "R34") (pin "1") (pinfunction "1_1") (pintype "passive"))
      (node (ref "U9") (pin "2") (pinfunction "NO1_2") (pintype "passive"))
    )
    (net (code "64") (name "Net-(U9-NO2)") (class "Default")
      (node (ref "NC") (pin "2") (pinfunction "2_2") (pintype "passive"))
      (node (ref "R9") (pin "1") (pinfunction "1_1") (pintype "passive"))
      (node (ref "U9") (pin "3") (pinfunction "NO2_3") (pintype "passive"))
    )
    (net (code "65") (name "VCC_+5V") (class "Default")
      (node (ref "C18") (pin "2") (pinfunction "2_2") (pintype "passive"))
      (node (ref "C19") (pin "2") (pinfunction "2_2") (pintype "passive"))
      (node (ref "C4") (pin "1") (pinfunction "1_1") (pintype "passive"))
      (node (ref "C5") (pin "1") (pinfunction "1_1") (pintype "passive"))
      (node (ref "C6") (pin "1") (pinfunction "1_1") (pintype "passive"))
      (node (ref "C8") (pin "2") (pinfunction "2_2") (pintype "passive"))
      (node (ref "C9") (pin "2") (pinfunction "2_2") (pintype "passive"))
      (node (ref "J2") (pin "1") (pinfunction "1_1") (pintype "passive"))
      (node (ref "J2") (pin "3") (pinfunction "3_3") (pintype "passive"))
      (node (ref "J2") (pin "5") (pinfunction "5_5") (pintype "passive"))
      (node (ref "J2") (pin "7") (pinfunction "7_7") (pintype "passive"))
      (node (ref "U2") (pin "2") (pinfunction "IN_2") (pintype "passive"))
      (node (ref "U3") (pin "16") (pinfunction "VDD_16") (pintype "passive"))
      (node (ref "U4") (pin "16") (pinfunction "VDD_16") (pintype "passive"))
      (node (ref "U5") (pin "4") (pinfunction "VCC_4") (pintype "passive"))
      (node (ref "U6") (pin "4") (pinfunction "VCC_4") (pintype "passive"))
      (node (ref "U7") (pin "4") (pinfunction "VCC_4") (pintype "passive"))
      (node (ref "U8") (pin "5") (pinfunction "V+_5") (pintype "passive"))
    )
    (net (code "66") (name "VCC_-5V") (class "Default")
      (node (ref "C10") (pin "2") (pinfunction "2_2") (pintype "passive"))
      (node (ref "C11") (pin "2") (pinfunction "2_2") (pintype "passive"))
      (node (ref "C2") (pin "1") (pinfunction "1_1") (pintype "passive"))
      (node (ref "U2") (pin "1") (pinfunction "OUT_1") (pintype "passive"))
      (node (ref "U4") (pin "12") (pinfunction "RESET_12") (pintype "passive"))
      (node (ref "U4") (pin "8") (pinfunction "VSS_8") (pintype "passive"))
      (node (ref "U5") (pin "11") (pinfunction "GND_11") (pintype "passive"))
      (node (ref "U6") (pin "11") (pinfunction "GND_11") (pintype "passive"))
      (node (ref "U7") (pin "11") (pinfunction "GND_11") (pintype "passive"))
      (node (ref "U8") (pin "2") (pinfunction "V-_2") (pintype "passive"))
    )
    (net (code "67") (name "VCC_3V3_MCU") (class "Default")
      (node (ref "C22") (pin "1") (pinfunction "1_1") (pintype "passive"))
      (node (ref "C3") (pin "2") (pinfunction "2_2") (pintype "passive"))
      (node (ref "D1") (pin "1") (pinfunction "A_1") (pintype "passive"))
      (node (ref "D2") (pin "1") (pinfunction "A_1") (pintype "passive"))
      (node (ref "D3") (pin "1") (pinfunction "A_1") (pintype "passive"))
      (node (ref "J4") (pin "7") (pinfunction "7_7") (pintype "passive"))
      (node (ref "R18") (pin "2") (pinfunction "2_2") (pintype "passive"))
      (node (ref "R22") (pin "2") (pinfunction "2_2") (pintype "passive"))
      (node (ref "R23") (pin "2") (pinfunction "2_2") (pintype "passive"))
      (node (ref "R24") (pin "2") (pinfunction "2_2") (pintype "passive"))
      (node (ref "R25") (pin "2") (pinfunction "2_2") (pintype "passive"))
      (node (ref "U1") (pin "5") (pinfunction "COM_5") (pintype "passive"))
      (node (ref "U9") (pin "8") (pinfunction "VCC_8") (pintype "passive"))
    )
    (net (code "68") (name "unconnected-(U3-X1-Pad14)") (class "Default")
      (node (ref "U3") (pin "14") (pinfunction "X1_14") (pintype "passive+no_connect"))
    )
    (net (code "69") (name "unconnected-(U3-X3-Pad12)") (class "Default")
      (node (ref "U3") (pin "12") (pinfunction "X3_12") (pintype "passive+no_connect"))
    )
    (net (code "70") (name "unconnected-(U4-Q5-Pad5)") (class "Default")
      (node (ref "U4") (pin "5") (pinfunction "Q5_5") (pintype "passive"))
    )
    (net (code "71") (name "unconnected-(U4-Q6-Pad4)") (class "Default")
      (node (ref "U4") (pin "4") (pinfunction "Q6_4") (pintype "passive"))
    )
    (net (code "72") (name "unconnected-(U4-Q7-Pad6)") (class "Default")
      (node (ref "U4") (pin "6") (pinfunction "Q7_6") (pintype "passive"))
    )
    (net (code "73") (name "unconnected-(U4-Q8-Pad14)") (class "Default")
      (node (ref "U4") (pin "14") (pinfunction "Q8_14") (pintype "passive"))
    )
    (net (code "74") (name "unconnected-(U4-Q9-Pad13)") (class "Default")
      (node (ref "U4") (pin "13") (pinfunction "Q9_13") (pintype "passive"))
    )
    (net (code "75") (name "unconnected-(U4-Q10-Pad15)") (class "Default")
      (node (ref "U4") (pin "15") (pinfunction "Q10_15") (pintype "passive"))
    )
    (net (code "76") (name "unconnected-(U4-Q12-Pad1)") (class "Default")
      (node (ref "U4") (pin "1") (pinfunction "Q12_1") (pintype "passive"))
    )
    (net (code "77") (name "unconnected-(U4-Q13-Pad2)") (class "Default")
      (node (ref "U4") (pin "2") (pinfunction "Q13_2") (pintype "passive"))
    )
    (net (code "78") (name "unconnected-(U4-Q14-Pad3)") (class "Default")
      (node (ref "U4") (pin "3") (pinfunction "Q14_3") (pintype "passive"))
    )
  )
)
